# RX-FM-Radio-1_5V-dip.net
KiCad netlist of a schematic drawn in EAGLE
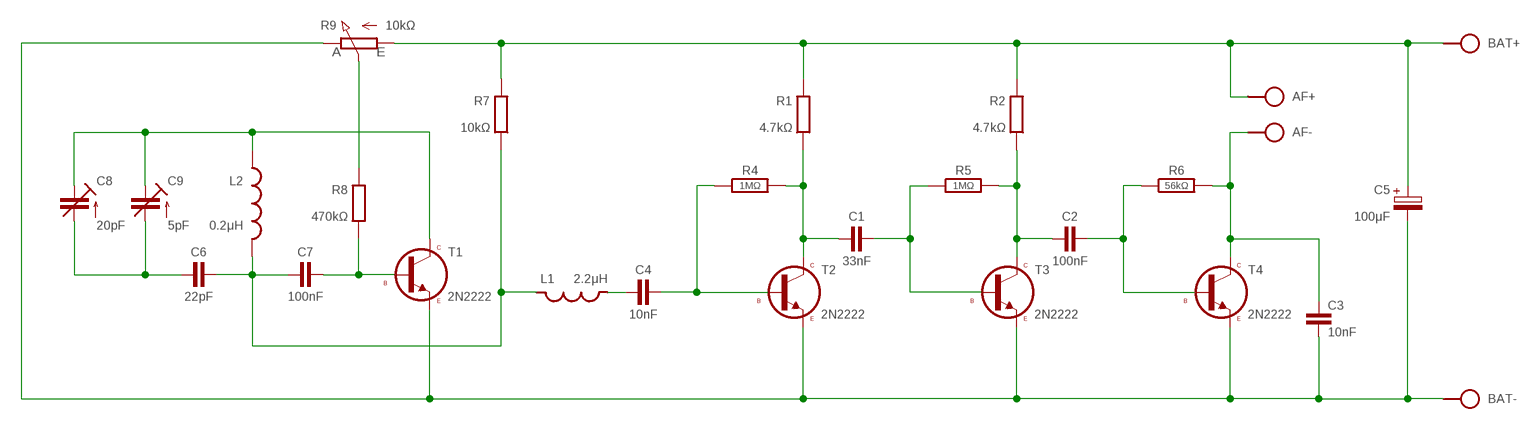
[diagram p0: schematic, sheet 1]

(export (version "E")
  (design (tool "Eeschema 10.0.6"))
  (components
    (comp (ref "AF")
      (value "SPAD+-+-")
      (footprint "eagle-import:SPAD+-")
      (libsource (lib "eagle-import") (part "SPAD+-+-"))
    )
    (comp (ref "BAT")
      (value "SPAD+-+-")
      (footprint "eagle-import:SPAD+-")
      (libsource (lib "eagle-import") (part "SPAD+-+-"))
    )
    (comp (ref "C1")
      (value "33nF")
      (footprint "eagle-import:C050-020X044")
      (libsource (lib "eagle-import") (part "C-H050-020X044"))
    )
    (comp (ref "C2")
      (value "100nF")
      (footprint "eagle-import:C050-020X044")
      (libsource (lib "eagle-import") (part "C-H050-020X044"))
    )
    (comp (ref "C3")
      (value "10nF")
      (footprint "eagle-import:C050-025X060")
      (libsource (lib "eagle-import") (part "C025-025X060"))
    )
    (comp (ref "C4")
      (value "10nF")
      (footprint "eagle-import:C050-020X044")
      (libsource (lib "eagle-import") (part "C-H050-020X044"))
    )
    (comp (ref "C5")
      (value "100μF")
      (footprint "eagle-import:E2.5-4_V")
      (libsource (lib "eagle-import") (part "CPOLE2,5-4/V"))
    )
    (comp (ref "C6")
      (value "22pF")
      (footprint "eagle-import:C050-020X036")
      (libsource (lib "eagle-import") (part "C-H050-020X036"))
    )
    (comp (ref "C7")
      (value "100nF")
      (footprint "eagle-import:C050-020X044_V")
      (libsource (lib "eagle-import") (part "C-H050-020X044/V"))
    )
    (comp (ref "C8")
      (value "20pF")
      (footprint "eagle-import:TRIM-2222-808")
      (libsource (lib "eagle-import") (part "C-TR-PH201272222-808-2PIND"))
    )
    (comp (ref "C9")
      (value "5pF")
      (footprint "eagle-import:CTRIMTZ03")
      (libsource (lib "eagle-import") (part "C-TR-PH20127-TZ03"))
    )
    (comp (ref "L1")
      (value "2.2μH")
      (footprint "eagle-import:L-03_10")
      (libsource (lib "eagle-import") (part "L-H-SHORT-03/10"))
    )
    (comp (ref "L2")
      (value "0.2μH")
      (footprint "eagle-import:L-10_10Y")
      (libsource (lib "eagle-import") (part "L10/10Y"))
    )
    (comp (ref "R1")
      (value "4.7kΩ")
      (footprint "eagle-import:0204_10-V")
      (libsource (lib "eagle-import") (part "R0204/10-V"))
    )
    (comp (ref "R2")
      (value "4.7kΩ")
      (footprint "eagle-import:0204_10-V")
      (libsource (lib "eagle-import") (part "R0204/10-V"))
    )
    (comp (ref "R4")
      (value "1MΩ")
      (footprint "eagle-import:0204_10-V")
      (libsource (lib "eagle-import") (part "R-H0204/10-V"))
    )
    (comp (ref "R5")
      (value "1MΩ")
      (footprint "eagle-import:0204_10-V")
      (libsource (lib "eagle-import") (part "R-H0204/10-V"))
    )
    (comp (ref "R6")
      (value "56kΩ")
      (footprint "eagle-import:0204_10-V")
      (libsource (lib "eagle-import") (part "R-H0204/10-V"))
    )
    (comp (ref "R7")
      (value "10kΩ")
      (footprint "eagle-import:0204_10-V")
      (libsource (lib "eagle-import") (part "R0204/10-V"))
    )
    (comp (ref "R8")
      (value "470kΩ")
      (footprint "eagle-import:0204_10-V")
      (libsource (lib "eagle-import") (part "R0204/10-V"))
    )
    (comp (ref "R9")
      (value "10kΩ")
      (footprint "eagle-import:CONN-3P")
      (libsource (lib "eagle-import") (part "POT-H-3P"))
    )
    (comp (ref "T1")
      (value "2N2222")
      (footprint "eagle-import:TO92")
      (libsource (lib "eagle-import") (part "2N2222"))
    )
    (comp (ref "T2")
      (value "2N2222")
      (footprint "eagle-import:TO92")
      (libsource (lib "eagle-import") (part "2N2222"))
    )
    (comp (ref "T3")
      (value "2N2222")
      (footprint "eagle-import:TO92")
      (libsource (lib "eagle-import") (part "2N2222"))
    )
    (comp (ref "T4")
      (value "2N2222")
      (footprint "eagle-import:TO92")
      (libsource (lib "eagle-import") (part "2N2222"))
    )
  )
  (nets
    (net (code "1") (name "Net-(AFA-P$1)") (class "Default")
      (node (ref "AF") (pin "2") (pinfunction "P$1_2") (pintype "passive"))
      (node (ref "BAT") (pin "2") (pinfunction "P$1_2") (pintype "passive"))
      (node (ref "C5") (pin "+") (pinfunction "+_+") (pintype "passive"))
      (node (ref "R1") (pin "1") (pinfunction "2_1") (pintype "passive"))
      (node (ref "R2") (pin "1") (pinfunction "2_1") (pintype "passive"))
      (node (ref "R7") (pin "1") (pinfunction "2_1") (pintype "passive"))
      (node (ref "R9") (pin "1") (pinfunction "A_1") (pintype "passive"))
    )
    (net (code "2") (name "Net-(AFB-P$1)") (class "Default")
      (node (ref "AF") (pin "1") (pinfunction "P$1_1") (pintype "passive"))
      (node (ref "C3") (pin "1") (pinfunction "1_1") (pintype "passive"))
      (node (ref "R6") (pin "2") (pinfunction "2_2") (pintype "passive"))
      (node (ref "T4") (pin "3") (pinfunction "C_3") (pintype "passive"))
    )
    (net (code "3") (name "Net-(BATB-P$1)") (class "Default")
      (node (ref "BAT") (pin "1") (pinfunction "P$1_1") (pintype "passive"))
      (node (ref "C3") (pin "2") (pinfunction "2_2") (pintype "passive"))
      (node (ref "C5") (pin "-") (pinfunction "-_-") (pintype "passive"))
      (node (ref "R9") (pin "3") (pinfunction "E_3") (pintype "passive"))
      (node (ref "T1") (pin "1") (pinfunction "E_1") (pintype "passive"))
      (node (ref "T2") (pin "1") (pinfunction "E_1") (pintype "passive"))
      (node (ref "T3") (pin "1") (pinfunction "E_1") (pintype "passive"))
      (node (ref "T4") (pin "1") (pinfunction "E_1") (pintype "passive"))
    )
    (net (code "4") (name "Net-(C4-Pad1)") (class "Default")
      (node (ref "C4") (pin "1") (pinfunction "1_1") (pintype "passive"))
      (node (ref "L1") (pin "1") (pinfunction "1_1") (pintype "passive"))
    )
    (net (code "5") (name "Net-(C8-A)") (class "Default")
      (node (ref "C6") (pin "1") (pinfunction "1_1") (pintype "passive"))
      (node (ref "C8") (pin "2") (pinfunction "A_2") (pintype "passive"))
      (node (ref "C9") (pin "1") (pinfunction "A_1") (pintype "passive"))
    )
    (net (code "6") (name "Net-(C8-E)") (class "Default")
      (node (ref "C8") (pin "3") (pinfunction "E_3") (pintype "passive"))
      (node (ref "C9") (pin "2") (pinfunction "E_2") (pintype "passive"))
      (node (ref "L2") (pin "P$1") (pinfunction "1_P$1") (pintype "passive"))
      (node (ref "T1") (pin "3") (pinfunction "C_3") (pintype "passive"))
    )
    (net (code "7") (name "Net-(L2-2)") (class "Default")
      (node (ref "C6") (pin "2") (pinfunction "2_2") (pintype "passive"))
      (node (ref "C7") (pin "1") (pinfunction "1_1") (pintype "passive"))
      (node (ref "L1") (pin "2") (pinfunction "2_2") (pintype "passive"))
      (node (ref "L2") (pin "P$2") (pinfunction "2_P$2") (pintype "passive"))
      (node (ref "R7") (pin "2") (pinfunction "1_2") (pintype "passive"))
    )
    (net (code "8") (name "Net-(R1-1)") (class "Default")
      (node (ref "C1") (pin "1") (pinfunction "1_1") (pintype "passive"))
      (node (ref "R1") (pin "2") (pinfunction "1_2") (pintype "passive"))
      (node (ref "R4") (pin "2") (pinfunction "2_2") (pintype "passive"))
      (node (ref "T2") (pin "3") (pinfunction "C_3") (pintype "passive"))
    )
    (net (code "9") (name "Net-(R2-1)") (class "Default")
      (node (ref "C2") (pin "1") (pinfunction "1_1") (pintype "passive"))
      (node (ref "R2") (pin "2") (pinfunction "1_2") (pintype "passive"))
      (node (ref "R5") (pin "2") (pinfunction "2_2") (pintype "passive"))
      (node (ref "T3") (pin "3") (pinfunction "C_3") (pintype "passive"))
    )
    (net (code "10") (name "Net-(R8-1)") (class "Default")
      (node (ref "C7") (pin "2") (pinfunction "2_2") (pintype "passive"))
      (node (ref "R8") (pin "2") (pinfunction "1_2") (pintype "passive"))
      (node (ref "T1") (pin "2") (pinfunction "B_2") (pintype "passive"))
    )
    (net (code "11") (name "Net-(R8-2)") (class "Default")
      (node (ref "R8") (pin "1") (pinfunction "2_1") (pintype "passive"))
      (node (ref "R9") (pin "2") (pinfunction "S_2") (pintype "passive"))
    )
    (net (code "12") (name "Net-(T2-B)") (class "Default")
      (node (ref "C4") (pin "2") (pinfunction "2_2") (pintype "passive"))
      (node (ref "R4") (pin "1") (pinfunction "1_1") (pintype "passive"))
      (node (ref "T2") (pin "2") (pinfunction "B_2") (pintype "passive"))
    )
    (net (code "13") (name "Net-(T3-B)") (class "Default")
      (node (ref "C1") (pin "2") (pinfunction "2_2") (pintype "passive"))
      (node (ref "R5") (pin "1") (pinfunction "1_1") (pintype "passive"))
      (node (ref "T3") (pin "2") (pinfunction "B_2") (pintype "passive"))
    )
    (net (code "14") (name "Net-(T4-B)") (class "Default")
      (node (ref "C2") (pin "2") (pinfunction "2_2") (pintype "passive"))
      (node (ref "R6") (pin "1") (pinfunction "1_1") (pintype "passive"))
      (node (ref "T4") (pin "2") (pinfunction "B_2") (pintype "passive"))
    )
  )
)
